# Sheet2.net
KiCad netlist of a schematic drawn in Altium Designer
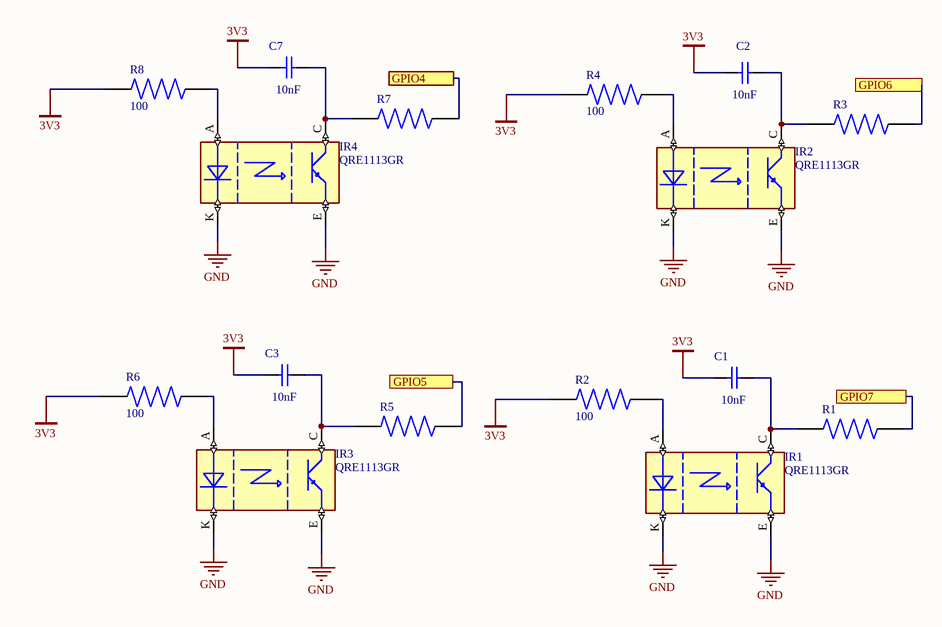
[diagram p0: Sheet2.SchDoc]

(export (version "E")
  (design (tool "Eeschema 10.0.6"))
  (components
    (comp (ref "C1")
      (value "10nF")
      (footprint "WCAP-CSGP_0805_L2W1.25H1.25")
      (description "WCAP-CSGP Multilayer Ceramic Chip Capacitor, General Purpose, size 0805, NP0, 10nF, 10V")
      (fields
        (field (name "MANUFACTURER PART NUMBER") "885012007009")
        (field (name "MANUFACTURER") "Wurth Elektronik")
      )
      (libsource (lib "10nf_CAP_WCAP-CSGP") (part "885012007009"))
    )
    (comp (ref "C2")
      (value "10nF")
      (footprint "WCAP-CSGP_0805_L2W1.25H1.25")
      (description "WCAP-CSGP Multilayer Ceramic Chip Capacitor, General Purpose, size 0805, NP0, 10nF, 10V")
      (fields
        (field (name "MANUFACTURER PART NUMBER") "885012007009")
        (field (name "MANUFACTURER") "Wurth Elektronik")
      )
      (libsource (lib "10nf_CAP_WCAP-CSGP") (part "885012007009"))
    )
    (comp (ref "C3")
      (value "10nF")
      (footprint "WCAP-CSGP_0805_L2W1.25H1.25")
      (description "WCAP-CSGP Multilayer Ceramic Chip Capacitor, General Purpose, size 0805, NP0, 10nF, 10V")
      (fields
        (field (name "MANUFACTURER PART NUMBER") "885012007009")
        (field (name "MANUFACTURER") "Wurth Elektronik")
      )
      (libsource (lib "10nf_CAP_WCAP-CSGP") (part "885012007009"))
    )
    (comp (ref "C7")
      (value "10nF")
      (footprint "WCAP-CSGP_0805_L2W1.25H1.25")
      (description "WCAP-CSGP Multilayer Ceramic Chip Capacitor, General Purpose, size 0805, NP0, 10nF, 10V")
      (fields
        (field (name "MANUFACTURER PART NUMBER") "885012007009")
        (field (name "MANUFACTURER") "Wurth Elektronik")
      )
      (libsource (lib "10nf_CAP_WCAP-CSGP") (part "885012007009"))
    )
    (comp (ref "IR1")
      (value "QRE1113GR")
      (footprint "4LEADSMD")
      (description "Optical Switches, Reflective, Phototransistor Output Reflective Sensor")
      (fields (field (name "MF") "SparkFun") (field (name "MP") "QRE1113"))
      (libsource (lib "QRE1113GR") (part "QRE1113GR"))
    )
    (comp (ref "IR2")
      (value "QRE1113GR")
      (footprint "4LEADSMD")
      (description "Optical Switches, Reflective, Phototransistor Output Reflective Sensor")
      (fields (field (name "MF") "SparkFun") (field (name "MP") "QRE1113"))
      (libsource (lib "QRE1113GR") (part "QRE1113GR"))
    )
    (comp (ref "IR3")
      (value "QRE1113GR")
      (footprint "4LEADSMD")
      (description "Optical Switches, Reflective, Phototransistor Output Reflective Sensor")
      (fields (field (name "MF") "SparkFun") (field (name "MP") "QRE1113"))
      (libsource (lib "QRE1113GR") (part "QRE1113GR"))
    )
    (comp (ref "IR4")
      (value "QRE1113GR")
      (footprint "4LEADSMD")
      (description "Optical Switches, Reflective, Phototransistor Output Reflective Sensor")
      (fields (field (name "MF") "SparkFun") (field (name "MP") "QRE1113"))
      (libsource (lib "QRE1113GR") (part "QRE1113GR"))
    )
    (comp (ref "R1")
      (value "220")
      (footprint "RESC1005X35N")
      (fields
        (field (name "MF") "TE Connectivity")
        (field (name "MP") "CPF0402B220RE1")
        (field (name "TOLERANCE") ".1%")
      )
      (libsource (lib "220_ohm_CPF0402B220RE1") (part "CPF0402B220RE1"))
    )
    (comp (ref "R2")
      (value "100")
      (footprint "RESC6432X75N")
      (description "CRS Series Anti-surge Resistor 2512 Case 100Ohms 2W +/-100ppm/degC ¦ Bourns CRS2512-FX-1000ELF")
      (fields (field (name "MF") "Bourns") (field (name "MP") "CRS2512-FX-1000ELF"))
      (libsource (lib "100ohh") (part "CRS2512-FX-1000ELF"))
    )
    (comp (ref "R3")
      (value "220")
      (footprint "RESC1005X35N")
      (fields
        (field (name "MF") "TE Connectivity")
        (field (name "MP") "CPF0402B220RE1")
        (field (name "TOLERANCE") ".1%")
      )
      (libsource (lib "220_ohm_CPF0402B220RE1") (part "CPF0402B220RE1"))
    )
    (comp (ref "R4")
      (value "100")
      (footprint "RESC6432X75N")
      (description "CRS Series Anti-surge Resistor 2512 Case 100Ohms 2W +/-100ppm/degC ¦ Bourns CRS2512-FX-1000ELF")
      (fields (field (name "MF") "Bourns") (field (name "MP") "CRS2512-FX-1000ELF"))
      (libsource (lib "100ohh") (part "CRS2512-FX-1000ELF"))
    )
    (comp (ref "R5")
      (value "220")
      (footprint "RESC1005X35N")
      (fields
        (field (name "MF") "TE Connectivity")
        (field (name "MP") "CPF0402B220RE1")
        (field (name "TOLERANCE") ".1%")
      )
      (libsource (lib "220_ohm_CPF0402B220RE1") (part "CPF0402B220RE1"))
    )
    (comp (ref "R6")
      (value "100")
      (footprint "RESC6432X75N")
      (description "CRS Series Anti-surge Resistor 2512 Case 100Ohms 2W +/-100ppm/degC ¦ Bourns CRS2512-FX-1000ELF")
      (fields (field (name "MF") "Bourns") (field (name "MP") "CRS2512-FX-1000ELF"))
      (libsource (lib "100ohh") (part "CRS2512-FX-1000ELF"))
    )
    (comp (ref "R7")
      (value "220")
      (footprint "RESC1005X35N")
      (fields
        (field (name "MF") "TE Connectivity")
        (field (name "MP") "CPF0402B220RE1")
        (field (name "TOLERANCE") ".1%")
      )
      (libsource (lib "220_ohm_CPF0402B220RE1") (part "CPF0402B220RE1"))
    )
    (comp (ref "R8")
      (value "100")
      (footprint "RESC6432X75N")
      (description "CRS Series Anti-surge Resistor 2512 Case 100Ohms 2W +/-100ppm/degC ¦ Bourns CRS2512-FX-1000ELF")
      (fields (field (name "MF") "Bourns") (field (name "MP") "CRS2512-FX-1000ELF"))
      (libsource (lib "100ohh") (part "CRS2512-FX-1000ELF"))
    )
  )
  (nets
    (net (code "1") (name "/GPIO4") (class "Default")
      (node (ref "R7") (pin "2") (pinfunction "2_2") (pintype "passive"))
    )
    (net (code "2") (name "/GPIO5") (class "Default")
      (node (ref "R5") (pin "2") (pinfunction "2_2") (pintype "passive"))
    )
    (net (code "3") (name "/GPIO6") (class "Default")
      (node (ref "R3") (pin "2") (pinfunction "2_2") (pintype "passive"))
    )
    (net (code "4") (name "/GPIO7") (class "Default")
      (node (ref "R1") (pin "2") (pinfunction "2_2") (pintype "passive"))
    )
    (net (code "5") (name "3V3") (class "Default")
      (node (ref "C1") (pin "1") (pinfunction "1_1") (pintype "passive"))
      (node (ref "C2") (pin "1") (pinfunction "1_1") (pintype "passive"))
      (node (ref "C3") (pin "1") (pinfunction "1_1") (pintype "passive"))
      (node (ref "C7") (pin "1") (pinfunction "1_1") (pintype "passive"))
      (node (ref "R2") (pin "1") (pinfunction "1_1") (pintype "passive"))
      (node (ref "R4") (pin "1") (pinfunction "1_1") (pintype "passive"))
      (node (ref "R6") (pin "1") (pinfunction "1_1") (pintype "passive"))
      (node (ref "R8") (pin "1") (pinfunction "1_1") (pintype "passive"))
    )
    (net (code "6") (name "GND") (class "Default")
      (node (ref "IR1") (pin "E") (pinfunction "E_E") (pintype "bidirectional"))
      (node (ref "IR1") (pin "K") (pinfunction "K_K") (pintype "bidirectional"))
      (node (ref "IR2") (pin "E") (pinfunction "E_E") (pintype "bidirectional"))
      (node (ref "IR2") (pin "K") (pinfunction "K_K") (pintype "bidirectional"))
      (node (ref "IR3") (pin "E") (pinfunction "E_E") (pintype "bidirectional"))
      (node (ref "IR3") (pin "K") (pinfunction "K_K") (pintype "bidirectional"))
      (node (ref "IR4") (pin "E") (pinfunction "E_E") (pintype "bidirectional"))
      (node (ref "IR4") (pin "K") (pinfunction "K_K") (pintype "bidirectional"))
    )
    (net (code "7") (name "Net-(C1-Pad2)") (class "Default")
      (node (ref "C1") (pin "2") (pinfunction "2_2") (pintype "passive"))
      (node (ref "IR1") (pin "C") (pinfunction "C_C") (pintype "bidirectional"))
      (node (ref "R1") (pin "1") (pinfunction "1_1") (pintype "passive"))
    )
    (net (code "8") (name "Net-(C2-Pad2)") (class "Default")
      (node (ref "C2") (pin "2") (pinfunction "2_2") (pintype "passive"))
      (node (ref "IR2") (pin "C") (pinfunction "C_C") (pintype "bidirectional"))
      (node (ref "R3") (pin "1") (pinfunction "1_1") (pintype "passive"))
    )
    (net (code "9") (name "Net-(C3-Pad2)") (class "Default")
      (node (ref "C3") (pin "2") (pinfunction "2_2") (pintype "passive"))
      (node (ref "IR3") (pin "C") (pinfunction "C_C") (pintype "bidirectional"))
      (node (ref "R5") (pin "1") (pinfunction "1_1") (pintype "passive"))
    )
    (net (code "10") (name "Net-(C7-Pad2)") (class "Default")
      (node (ref "C7") (pin "2") (pinfunction "2_2") (pintype "passive"))
      (node (ref "IR4") (pin "C") (pinfunction "C_C") (pintype "bidirectional"))
      (node (ref "R7") (pin "1") (pinfunction "1_1") (pintype "passive"))
    )
    (net (code "11") (name "Net-(IR1-PadA)") (class "Default")
      (node (ref "IR1") (pin "A") (pinfunction "A_A") (pintype "bidirectional"))
      (node (ref "R2") (pin "2") (pinfunction "2_2") (pintype "passive"))
    )
    (net (code "12") (name "Net-(IR2-PadA)") (class "Default")
      (node (ref "IR2") (pin "A") (pinfunction "A_A") (pintype "bidirectional"))
      (node (ref "R4") (pin "2") (pinfunction "2_2") (pintype "passive"))
    )
    (net (code "13") (name "Net-(IR3-PadA)") (class "Default")
      (node (ref "IR3") (pin "A") (pinfunction "A_A") (pintype "bidirectional"))
      (node (ref "R6") (pin "2") (pinfunction "2_2") (pintype "passive"))
    )
    (net (code "14") (name "Net-(IR4-PadA)") (class "Default")
      (node (ref "IR4") (pin "A") (pinfunction "A_A") (pintype "bidirectional"))
      (node (ref "R8") (pin "2") (pinfunction "2_2") (pintype "passive"))
    )
  )
)
